# MicrophoneSoundModule.net
KiCad netlist of a schematic drawn in EAGLE
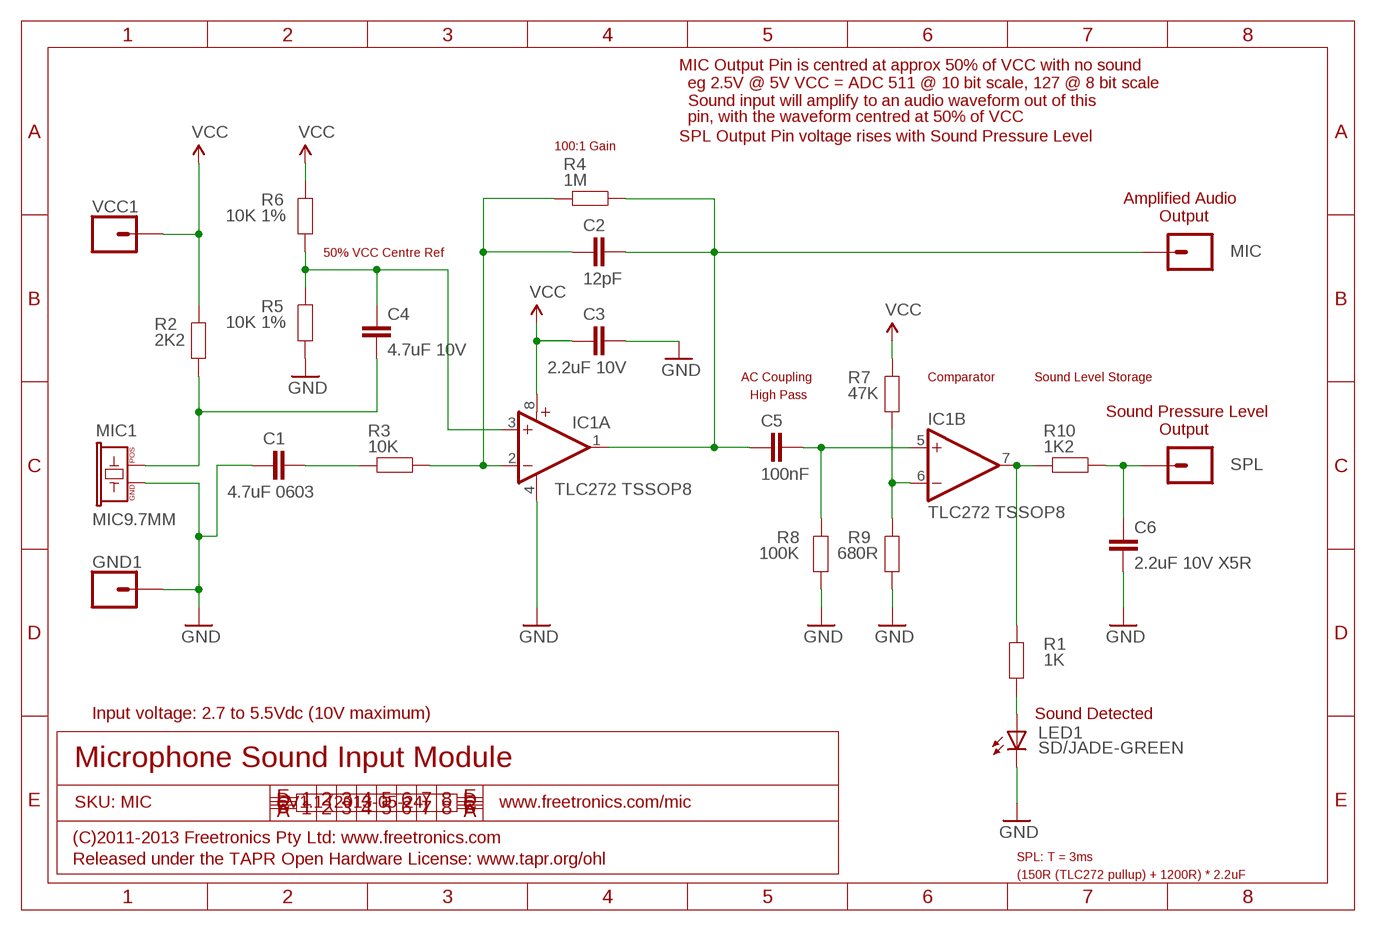
[diagram p0: schematic, sheet 1]

(export (version "E")
  (design (tool "Eeschema 10.0.6"))
  (components
    (comp (ref "C1")
      (value "4.7uF 0603")
      (footprint "eagle-import:0603")
      (libsource (lib "eagle-import") (part "CAP0603"))
    )
    (comp (ref "C2")
      (value "12pF")
      (footprint "eagle-import:0603")
      (libsource (lib "eagle-import") (part "CAP0603"))
    )
    (comp (ref "C3")
      (value "2.2uF 10V")
      (footprint "eagle-import:0603")
      (libsource (lib "eagle-import") (part "CAP0603"))
    )
    (comp (ref "C4")
      (value "4.7uF 10V")
      (footprint "eagle-import:0603")
      (libsource (lib "eagle-import") (part "CAP0603"))
    )
    (comp (ref "C5")
      (value "100nF")
      (footprint "eagle-import:0603")
      (libsource (lib "eagle-import") (part "CAP0603"))
    )
    (comp (ref "C6")
      (value "2.2uF 10V X5R")
      (footprint "eagle-import:0603")
      (libsource (lib "eagle-import") (part "CAP0603"))
    )
    (comp (ref "GND1")
      (value "M01PTH")
      (footprint "eagle-import:1X01")
      (libsource (lib "eagle-import") (part "M01PTH"))
    )
    (comp (ref "IC1")
      (value "TLC272 TSSOP8")
      (footprint "eagle-import:TSSOP8")
      (libsource (lib "eagle-import") (part "OPAMP-DUALTSSOP8"))
    )
    (comp (ref "LED1")
      (value "SD/JADE-GREEN")
      (footprint "eagle-import:LED-0603")
      (libsource (lib "eagle-import") (part "LED0603"))
    )
    (comp (ref "MIC")
      (value "M01PTH")
      (footprint "eagle-import:1X01")
      (libsource (lib "eagle-import") (part "M01PTH"))
    )
    (comp (ref "MIC1")
      (value "MIC9.7MM")
      (footprint "eagle-import:MIC-9.7MM")
      (libsource (lib "eagle-import") (part "MIC9.7MM"))
    )
    (comp (ref "R1")
      (value "1K")
      (footprint "eagle-import:0603")
      (libsource (lib "eagle-import") (part "RESISTOR0603"))
    )
    (comp (ref "R2")
      (value "2K2")
      (footprint "eagle-import:0603")
      (libsource (lib "eagle-import") (part "RESISTOR0603"))
    )
    (comp (ref "R3")
      (value "10K")
      (footprint "eagle-import:0603")
      (libsource (lib "eagle-import") (part "RESISTOR0603"))
    )
    (comp (ref "R4")
      (value "1M")
      (footprint "eagle-import:0603")
      (libsource (lib "eagle-import") (part "RESISTOR0603"))
    )
    (comp (ref "R5")
      (value "10K 1%")
      (footprint "eagle-import:0603")
      (libsource (lib "eagle-import") (part "RESISTOR0603"))
    )
    (comp (ref "R6")
      (value "10K 1%")
      (footprint "eagle-import:0603")
      (libsource (lib "eagle-import") (part "RESISTOR0603"))
    )
    (comp (ref "R7")
      (value "47K")
      (footprint "eagle-import:0603")
      (libsource (lib "eagle-import") (part "RESISTOR0603"))
    )
    (comp (ref "R8")
      (value "100K")
      (footprint "eagle-import:0603")
      (libsource (lib "eagle-import") (part "RESISTOR0603"))
    )
    (comp (ref "R9")
      (value "680R")
      (footprint "eagle-import:0603")
      (libsource (lib "eagle-import") (part "RESISTOR0603"))
    )
    (comp (ref "R10")
      (value "1K2")
      (footprint "eagle-import:0603")
      (libsource (lib "eagle-import") (part "RESISTOR0603"))
    )
    (comp (ref "SPL")
      (value "M01PTH")
      (footprint "eagle-import:1X01")
      (libsource (lib "eagle-import") (part "M01PTH"))
    )
    (comp (ref "VCC1")
      (value "M01PTH")
      (footprint "eagle-import:1X01")
      (libsource (lib "eagle-import") (part "M01PTH"))
    )
  )
  (nets
    (net (code "1") (name "GND") (class "Default")
      (node (ref "C1") (pin "1") (pinfunction "1_1") (pintype "passive"))
      (node (ref "C3") (pin "2") (pinfunction "2_2") (pintype "passive"))
      (node (ref "C6") (pin "1") (pinfunction "1_1") (pintype "passive"))
      (node (ref "GND1") (pin "1") (pinfunction "1_1") (pintype "passive"))
      (node (ref "IC1") (pin "4") (pinfunction "V-_4") (pintype "power_in"))
      (node (ref "LED1") (pin "C") (pinfunction "C_C") (pintype "passive"))
      (node (ref "MIC1") (pin "GND") (pinfunction "GND_GND") (pintype "passive"))
      (node (ref "R5") (pin "1") (pinfunction "1_1") (pintype "passive"))
      (node (ref "R8") (pin "1") (pinfunction "1_1") (pintype "passive"))
      (node (ref "R9") (pin "1") (pinfunction "1_1") (pintype "passive"))
    )
    (net (code "2") (name "Net-(C1-Pad2)") (class "Default")
      (node (ref "C1") (pin "2") (pinfunction "2_2") (pintype "passive"))
      (node (ref "R3") (pin "2") (pinfunction "2_2") (pintype "passive"))
    )
    (net (code "3") (name "Net-(C4-Pad1)") (class "Default")
      (node (ref "C4") (pin "1") (pinfunction "1_1") (pintype "passive"))
      (node (ref "MIC1") (pin "POS") (pinfunction "POS_POS") (pintype "passive"))
      (node (ref "R2") (pin "1") (pinfunction "1_1") (pintype "passive"))
    )
    (net (code "4") (name "Net-(C6-Pad2)") (class "Default")
      (node (ref "C6") (pin "2") (pinfunction "2_2") (pintype "passive"))
      (node (ref "R10") (pin "1") (pinfunction "1_1") (pintype "passive"))
      (node (ref "SPL") (pin "1") (pinfunction "1_1") (pintype "passive"))
    )
    (net (code "5") (name "Net-(IC1A-+IN)") (class "Default")
      (node (ref "C4") (pin "2") (pinfunction "2_2") (pintype "passive"))
      (node (ref "IC1") (pin "3") (pinfunction "+IN_3") (pintype "input"))
      (node (ref "R5") (pin "2") (pinfunction "2_2") (pintype "passive"))
      (node (ref "R6") (pin "1") (pinfunction "1_1") (pintype "passive"))
    )
    (net (code "6") (name "Net-(IC1A--IN)") (class "Default")
      (node (ref "C2") (pin "1") (pinfunction "1_1") (pintype "passive"))
      (node (ref "IC1") (pin "2") (pinfunction "-IN_2") (pintype "input"))
      (node (ref "R3") (pin "1") (pinfunction "1_1") (pintype "passive"))
      (node (ref "R4") (pin "2") (pinfunction "2_2") (pintype "passive"))
    )
    (net (code "7") (name "Net-(IC1A-OUT)") (class "Default")
      (node (ref "C2") (pin "2") (pinfunction "2_2") (pintype "passive"))
      (node (ref "C5") (pin "1") (pinfunction "1_1") (pintype "passive"))
      (node (ref "IC1") (pin "1") (pinfunction "OUT_1") (pintype "output"))
      (node (ref "MIC") (pin "1") (pinfunction "1_1") (pintype "passive"))
      (node (ref "R4") (pin "1") (pinfunction "1_1") (pintype "passive"))
    )
    (net (code "8") (name "Net-(IC1B-+IN)") (class "Default")
      (node (ref "C5") (pin "2") (pinfunction "2_2") (pintype "passive"))
      (node (ref "IC1") (pin "5") (pinfunction "+IN_5") (pintype "input"))
      (node (ref "R8") (pin "2") (pinfunction "2_2") (pintype "passive"))
    )
    (net (code "9") (name "Net-(IC1B--IN)") (class "Default")
      (node (ref "IC1") (pin "6") (pinfunction "-IN_6") (pintype "input"))
      (node (ref "R7") (pin "1") (pinfunction "1_1") (pintype "passive"))
      (node (ref "R9") (pin "2") (pinfunction "2_2") (pintype "passive"))
    )
    (net (code "10") (name "Net-(IC1B-OUT)") (class "Default")
      (node (ref "IC1") (pin "7") (pinfunction "OUT_7") (pintype "output"))
      (node (ref "R1") (pin "2") (pinfunction "2_2") (pintype "passive"))
      (node (ref "R10") (pin "2") (pinfunction "2_2") (pintype "passive"))
    )
    (net (code "11") (name "Net-(LED1-PadA)") (class "Default")
      (node (ref "LED1") (pin "A") (pinfunction "A_A") (pintype "passive"))
      (node (ref "R1") (pin "1") (pinfunction "1_1") (pintype "passive"))
    )
    (net (code "12") (name "VCC") (class "Default")
      (node (ref "C3") (pin "1") (pinfunction "1_1") (pintype "passive"))
      (node (ref "IC1") (pin "8") (pinfunction "V+_8") (pintype "power_in"))
      (node (ref "R2") (pin "2") (pinfunction "2_2") (pintype "passive"))
      (node (ref "R6") (pin "2") (pinfunction "2_2") (pintype "passive"))
      (node (ref "R7") (pin "2") (pinfunction "2_2") (pintype "passive"))
      (node (ref "VCC1") (pin "1") (pinfunction "1_1") (pintype "passive"))
    )
  )
)
